# Ffrydiau_core.net
KiCad netlist of a schematic drawn in EAGLE
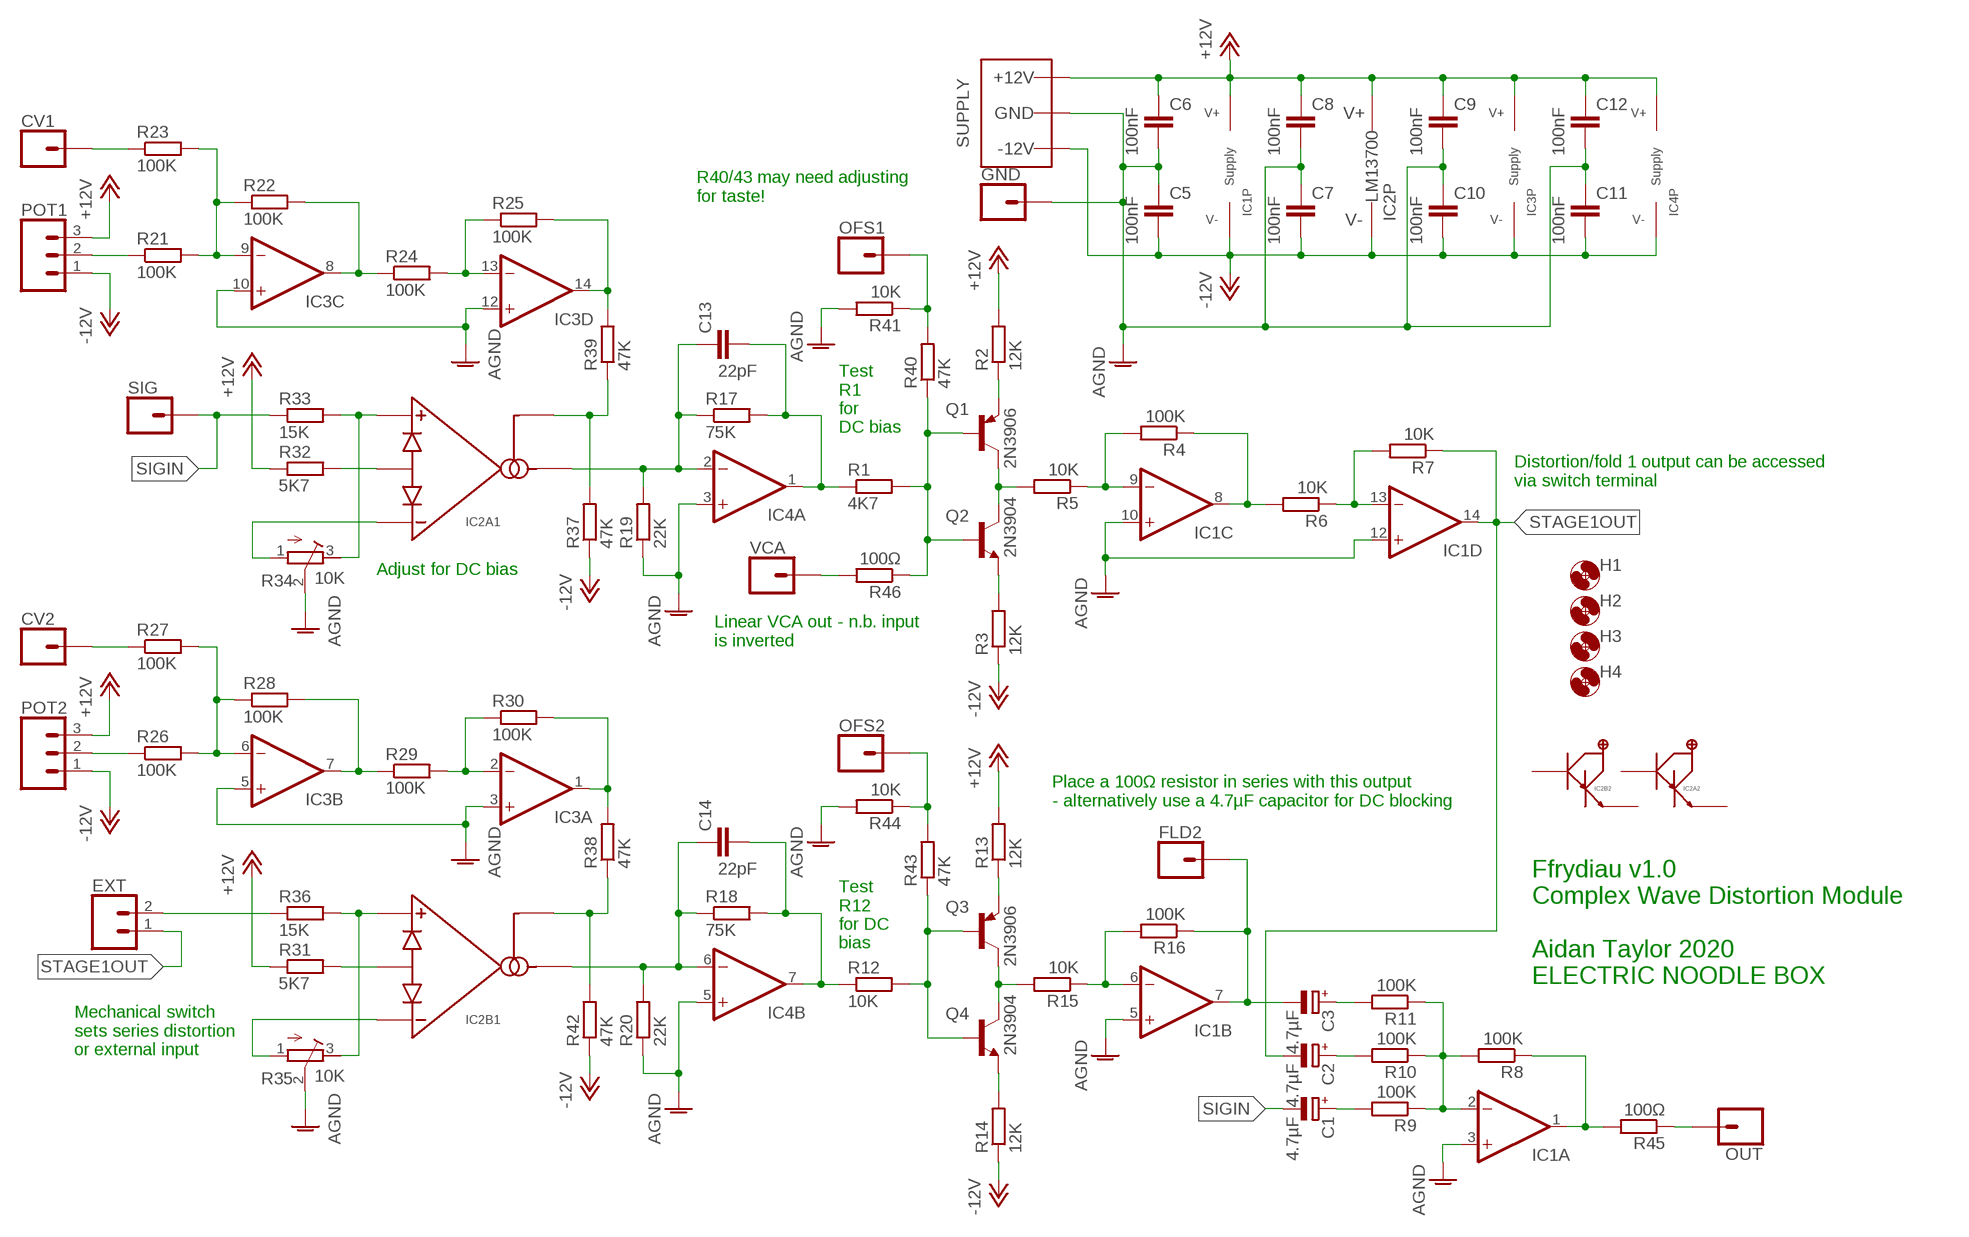
[diagram p0: schematic, sheet 1]

(export (version "E")
  (design (tool "Eeschema 10.0.6"))
  (components
    (comp (ref "C1")
      (value "4.7µF")
      (footprint "eagle-import:E2,5-6E")
      (libsource (lib "eagle-import") (part "CPOL-EUE2,5-6E"))
    )
    (comp (ref "C2")
      (value "4.7µF")
      (footprint "eagle-import:E2,5-6E")
      (libsource (lib "eagle-import") (part "CPOL-EUE2,5-6E"))
    )
    (comp (ref "C3")
      (value "4.7µF")
      (footprint "eagle-import:E2,5-6E")
      (libsource (lib "eagle-import") (part "CPOL-EUE2,5-6E"))
    )
    (comp (ref "C5")
      (value "100nF")
      (footprint "eagle-import:C050-025X075")
      (libsource (lib "eagle-import") (part "C-EU050-025X075"))
    )
    (comp (ref "C6")
      (value "100nF")
      (footprint "eagle-import:C050-025X075")
      (libsource (lib "eagle-import") (part "C-EU050-025X075"))
    )
    (comp (ref "C7")
      (value "100nF")
      (footprint "eagle-import:C050-025X075")
      (libsource (lib "eagle-import") (part "C-EU050-025X075"))
    )
    (comp (ref "C8")
      (value "100nF")
      (footprint "eagle-import:C050-025X075")
      (libsource (lib "eagle-import") (part "C-EU050-025X075"))
    )
    (comp (ref "C9")
      (value "100nF")
      (footprint "eagle-import:C050-025X075")
      (libsource (lib "eagle-import") (part "C-EU050-025X075"))
    )
    (comp (ref "C10")
      (value "100nF")
      (footprint "eagle-import:C050-025X075")
      (libsource (lib "eagle-import") (part "C-EU050-025X075"))
    )
    (comp (ref "C11")
      (value "100nF")
      (footprint "eagle-import:C050-025X075")
      (libsource (lib "eagle-import") (part "C-EU050-025X075"))
    )
    (comp (ref "C12")
      (value "100nF")
      (footprint "eagle-import:C050-025X075")
      (libsource (lib "eagle-import") (part "C-EU050-025X075"))
    )
    (comp (ref "C13")
      (value "22pF")
      (footprint "eagle-import:C050-025X075")
      (libsource (lib "eagle-import") (part "C-EU050-025X075"))
    )
    (comp (ref "C14")
      (value "22pF")
      (footprint "eagle-import:C050-025X075")
      (libsource (lib "eagle-import") (part "C-EU050-025X075"))
    )
    (comp (ref "CV1")
      (value "1XWIREPAD")
      (footprint "eagle-import:1X01")
      (libsource (lib "eagle-import") (part "1XWIREPAD"))
    )
    (comp (ref "CV2")
      (value "1XWIREPAD")
      (footprint "eagle-import:1X01")
      (libsource (lib "eagle-import") (part "1XWIREPAD"))
    )
    (comp (ref "EXT")
      (value "2XWIREPAD")
      (footprint "eagle-import:1X02")
      (libsource (lib "eagle-import") (part "2XWIREPAD"))
    )
    (comp (ref "FLD2")
      (value "1XWIREPAD")
      (footprint "eagle-import:1X01")
      (libsource (lib "eagle-import") (part "1XWIREPAD"))
    )
    (comp (ref "GND")
      (value "1XWIREPAD")
      (footprint "eagle-import:1X01")
      (libsource (lib "eagle-import") (part "1XWIREPAD"))
    )
    (comp (ref "H1")
      (value "MOUNT-HOLE3.2")
      (footprint "eagle-import:3,2")
      (libsource (lib "eagle-import") (part "MOUNT-HOLE3.2"))
    )
    (comp (ref "H2")
      (value "MOUNT-HOLE3.2")
      (footprint "eagle-import:3,2")
      (libsource (lib "eagle-import") (part "MOUNT-HOLE3.2"))
    )
    (comp (ref "H3")
      (value "MOUNT-HOLE3.2")
      (footprint "eagle-import:3,2")
      (libsource (lib "eagle-import") (part "MOUNT-HOLE3.2"))
    )
    (comp (ref "H4")
      (value "MOUNT-HOLE3.2")
      (footprint "eagle-import:3,2")
      (libsource (lib "eagle-import") (part "MOUNT-HOLE3.2"))
    )
    (comp (ref "IC1")
      (value "TL0X4DIL")
      (footprint "eagle-import:DIL14")
      (libsource (lib "eagle-import") (part "TL0X4DIL"))
    )
    (comp (ref "IC2")
      (value "LM13700DIL")
      (footprint "eagle-import:DIL16")
      (libsource (lib "eagle-import") (part "LM13700DIL"))
    )
    (comp (ref "IC3")
      (value "TL0X4DIL")
      (footprint "eagle-import:DIL14")
      (libsource (lib "eagle-import") (part "TL0X4DIL"))
    )
    (comp (ref "IC4")
      (value "TL0X2DIL")
      (footprint "eagle-import:DIL08")
      (libsource (lib "eagle-import") (part "TL0X2DIL"))
    )
    (comp (ref "OFS1")
      (value "1XWIREPAD")
      (footprint "eagle-import:1X01")
      (libsource (lib "eagle-import") (part "1XWIREPAD"))
    )
    (comp (ref "OFS2")
      (value "1XWIREPAD")
      (footprint "eagle-import:1X01")
      (libsource (lib "eagle-import") (part "1XWIREPAD"))
    )
    (comp (ref "OUT")
      (value "1XWIREPAD")
      (footprint "eagle-import:1X01")
      (libsource (lib "eagle-import") (part "1XWIREPAD"))
    )
    (comp (ref "POT1")
      (value "3XWIREPAD")
      (footprint "eagle-import:1X03")
      (libsource (lib "eagle-import") (part "3XWIREPAD"))
    )
    (comp (ref "POT2")
      (value "3XWIREPAD")
      (footprint "eagle-import:1X03")
      (libsource (lib "eagle-import") (part "3XWIREPAD"))
    )
    (comp (ref "Q1")
      (value "2N3906")
      (footprint "eagle-import:TO92")
      (libsource (lib "eagle-import") (part "2N3906"))
    )
    (comp (ref "Q2")
      (value "2N3904")
      (footprint "eagle-import:TO92")
      (libsource (lib "eagle-import") (part "2N3904"))
    )
    (comp (ref "Q3")
      (value "2N3906")
      (footprint "eagle-import:TO92")
      (libsource (lib "eagle-import") (part "2N3906"))
    )
    (comp (ref "Q4")
      (value "2N3904")
      (footprint "eagle-import:TO92")
      (libsource (lib "eagle-import") (part "2N3904"))
    )
    (comp (ref "R1")
      (value "4K7")
      (footprint "eagle-import:0207_10")
      (libsource (lib "eagle-import") (part "R-EU_0207/10"))
    )
    (comp (ref "R2")
      (value "12K")
      (footprint "eagle-import:0207_10")
      (libsource (lib "eagle-import") (part "R-EU_0207/10"))
    )
    (comp (ref "R3")
      (value "12K")
      (footprint "eagle-import:0207_10")
      (libsource (lib "eagle-import") (part "R-EU_0207/10"))
    )
    (comp (ref "R4")
      (value "100K")
      (footprint "eagle-import:0207_10")
      (libsource (lib "eagle-import") (part "R-EU_0207/10"))
    )
    (comp (ref "R5")
      (value "10K")
      (footprint "eagle-import:0207_10")
      (libsource (lib "eagle-import") (part "R-EU_0207/10"))
    )
    (comp (ref "R6")
      (value "10K")
      (footprint "eagle-import:0207_10")
      (libsource (lib "eagle-import") (part "R-EU_0207/10"))
    )
    (comp (ref "R7")
      (value "10K")
      (footprint "eagle-import:0207_10")
      (libsource (lib "eagle-import") (part "R-EU_0207/10"))
    )
    (comp (ref "R8")
      (value "100K")
      (footprint "eagle-import:0207_10")
      (libsource (lib "eagle-import") (part "R-EU_0207/10"))
    )
    (comp (ref "R9")
      (value "100K")
      (footprint "eagle-import:0207_10")
      (libsource (lib "eagle-import") (part "R-EU_0207/10"))
    )
    (comp (ref "R10")
      (value "100K")
      (footprint "eagle-import:0207_10")
      (libsource (lib "eagle-import") (part "R-EU_0207/10"))
    )
    (comp (ref "R11")
      (value "100K")
      (footprint "eagle-import:0207_10")
      (libsource (lib "eagle-import") (part "R-EU_0207/10"))
    )
    (comp (ref "R12")
      (value "10K")
      (footprint "eagle-import:0207_10")
      (libsource (lib "eagle-import") (part "R-EU_0207/10"))
    )
    (comp (ref "R13")
      (value "12K")
      (footprint "eagle-import:0207_10")
      (libsource (lib "eagle-import") (part "R-EU_0207/10"))
    )
    (comp (ref "R14")
      (value "12K")
      (footprint "eagle-import:0207_10")
      (libsource (lib "eagle-import") (part "R-EU_0207/10"))
    )
    (comp (ref "R15")
      (value "10K")
      (footprint "eagle-import:0207_10")
      (libsource (lib "eagle-import") (part "R-EU_0207/10"))
    )
    (comp (ref "R16")
      (value "100K")
      (footprint "eagle-import:0207_10")
      (libsource (lib "eagle-import") (part "R-EU_0207/10"))
    )
    (comp (ref "R17")
      (value "75K")
      (footprint "eagle-import:0207_10")
      (libsource (lib "eagle-import") (part "R-EU_0207/10"))
    )
    (comp (ref "R18")
      (value "75K")
      (footprint "eagle-import:0207_10")
      (libsource (lib "eagle-import") (part "R-EU_0207/10"))
    )
    (comp (ref "R19")
      (value "22K")
      (footprint "eagle-import:0207_10")
      (libsource (lib "eagle-import") (part "R-EU_0207/10"))
    )
    (comp (ref "R20")
      (value "22K")
      (footprint "eagle-import:0207_10")
      (libsource (lib "eagle-import") (part "R-EU_0207/10"))
    )
    (comp (ref "R21")
      (value "100K")
      (footprint "eagle-import:0207_10")
      (libsource (lib "eagle-import") (part "R-EU_0207/10"))
    )
    (comp (ref "R22")
      (value "100K")
      (footprint "eagle-import:0207_10")
      (libsource (lib "eagle-import") (part "R-EU_0207/10"))
    )
    (comp (ref "R23")
      (value "100K")
      (footprint "eagle-import:0207_10")
      (libsource (lib "eagle-import") (part "R-EU_0207/10"))
    )
    (comp (ref "R24")
      (value "100K")
      (footprint "eagle-import:0207_10")
      (libsource (lib "eagle-import") (part "R-EU_0207/10"))
    )
    (comp (ref "R25")
      (value "100K")
      (footprint "eagle-import:0207_10")
      (libsource (lib "eagle-import") (part "R-EU_0207/10"))
    )
    (comp (ref "R26")
      (value "100K")
      (footprint "eagle-import:0207_10")
      (libsource (lib "eagle-import") (part "R-EU_0207/10"))
    )
    (comp (ref "R27")
      (value "100K")
      (footprint "eagle-import:0207_10")
      (libsource (lib "eagle-import") (part "R-EU_0207/10"))
    )
    (comp (ref "R28")
      (value "100K")
      (footprint "eagle-import:0207_10")
      (libsource (lib "eagle-import") (part "R-EU_0207/10"))
    )
    (comp (ref "R29")
      (value "100K")
      (footprint "eagle-import:0207_10")
      (libsource (lib "eagle-import") (part "R-EU_0207/10"))
    )
    (comp (ref "R30")
      (value "100K")
      (footprint "eagle-import:0207_10")
      (libsource (lib "eagle-import") (part "R-EU_0207/10"))
    )
    (comp (ref "R31")
      (value "5K7")
      (footprint "eagle-import:0207_10")
      (libsource (lib "eagle-import") (part "R-EU_0207/10"))
    )
    (comp (ref "R32")
      (value "5K7")
      (footprint "eagle-import:0207_10")
      (libsource (lib "eagle-import") (part "R-EU_0207/10"))
    )
    (comp (ref "R33")
      (value "15K")
      (footprint "eagle-import:0207_10")
      (libsource (lib "eagle-import") (part "R-EU_0207/10"))
    )
    (comp (ref "R34")
      (value "10K")
      (footprint "eagle-import:RTRIM3296W")
      (libsource (lib "eagle-import") (part "R-TRIMM3296W"))
    )
    (comp (ref "R35")
      (value "10K")
      (footprint "eagle-import:RTRIM3296W")
      (libsource (lib "eagle-import") (part "R-TRIMM3296W"))
    )
    (comp (ref "R36")
      (value "15K")
      (footprint "eagle-import:0207_10")
      (libsource (lib "eagle-import") (part "R-EU_0207/10"))
    )
    (comp (ref "R37")
      (value "47K")
      (footprint "eagle-import:0207_10")
      (libsource (lib "eagle-import") (part "R-EU_0207/10"))
    )
    (comp (ref "R38")
      (value "47K")
      (footprint "eagle-import:0207_10")
      (libsource (lib "eagle-import") (part "R-EU_0207/10"))
    )
    (comp (ref "R39")
      (value "47K")
      (footprint "eagle-import:0207_10")
      (libsource (lib "eagle-import") (part "R-EU_0207/10"))
    )
    (comp (ref "R40")
      (value "47K")
      (footprint "eagle-import:0207_10")
      (libsource (lib "eagle-import") (part "R-EU_0207/10"))
    )
    (comp (ref "R41")
      (value "10K")
      (footprint "eagle-import:0207_10")
      (libsource (lib "eagle-import") (part "R-EU_0207/10"))
    )
    (comp (ref "R42")
      (value "47K")
      (footprint "eagle-import:0207_10")
      (libsource (lib "eagle-import") (part "R-EU_0207/10"))
    )
    (comp (ref "R43")
      (value "47K")
      (footprint "eagle-import:0207_10")
      (libsource (lib "eagle-import") (part "R-EU_0207/10"))
    )
    (comp (ref "R44")
      (value "10K")
      (footprint "eagle-import:0207_10")
      (libsource (lib "eagle-import") (part "R-EU_0207/10"))
    )
    (comp (ref "R45")
      (value "100Ω")
      (footprint "eagle-import:0207_10")
      (libsource (lib "eagle-import") (part "R-EU_0207/10"))
    )
    (comp (ref "R46")
      (value "100Ω")
      (footprint "eagle-import:0207_10")
      (libsource (lib "eagle-import") (part "R-EU_0207/10"))
    )
    (comp (ref "SIG")
      (value "1XWIREPAD")
      (footprint "eagle-import:1X01")
      (libsource (lib "eagle-import") (part "1XWIREPAD"))
    )
    (comp (ref "VCA")
      (value "1XWIREPAD")
      (footprint "eagle-import:1X01")
      (libsource (lib "eagle-import") (part "1XWIREPAD"))
    )
    (comp (ref "WP1")
      (value "COMBO_SUPPLY_HEADER")
      (footprint "eagle-import:COMBINED_POWER")
      (libsource (lib "eagle-import") (part "COMBO_SUPPLY_HEADER"))
    )
  )
  (nets
    (net (code "1") (name "+12V") (class "Default")
      (node (ref "C12") (pin "1") (pinfunction "1_1") (pintype "passive"))
      (node (ref "C6") (pin "1") (pinfunction "1_1") (pintype "passive"))
      (node (ref "C8") (pin "1") (pinfunction "1_1") (pintype "passive"))
      (node (ref "C9") (pin "1") (pinfunction "1_1") (pintype "passive"))
      (node (ref "IC1") (pin "4") (pinfunction "V+_4") (pintype "bidirectional"))
      (node (ref "IC2") (pin "11") (pinfunction "V+_11") (pintype "power_in"))
      (node (ref "IC3") (pin "4") (pinfunction "V+_4") (pintype "bidirectional"))
      (node (ref "IC4") (pin "8") (pinfunction "V+_8") (pintype "bidirectional"))
      (node (ref "POT1") (pin "3") (pinfunction "3_3") (pintype "passive"))
      (node (ref "POT2") (pin "3") (pinfunction "3_3") (pintype "passive"))
      (node (ref "R13") (pin "2") (pinfunction "2_2") (pintype "passive"))
      (node (ref "R2") (pin "2") (pinfunction "2_2") (pintype "passive"))
      (node (ref "R31") (pin "1") (pinfunction "1_1") (pintype "passive"))
      (node (ref "R32") (pin "1") (pinfunction "1_1") (pintype "passive"))
      (node (ref "WP1") (pin "V+1") (pinfunction "V++_V+1") (pintype "power_in"))
      (node (ref "WP1") (pin "V+2") (pinfunction "V++_V+2") (pintype "power_in"))
      (node (ref "WP1") (pin "V+3") (pinfunction "V++_V+3") (pintype "power_in"))
    )
    (net (code "2") (name "-12V") (class "Default")
      (node (ref "C10") (pin "2") (pinfunction "2_2") (pintype "passive"))
      (node (ref "C11") (pin "2") (pinfunction "2_2") (pintype "passive"))
      (node (ref "C5") (pin "2") (pinfunction "2_2") (pintype "passive"))
      (node (ref "C7") (pin "2") (pinfunction "2_2") (pintype "passive"))
      (node (ref "IC1") (pin "11") (pinfunction "V-_11") (pintype "bidirectional"))
      (node (ref "IC2") (pin "6") (pinfunction "V-_6") (pintype "power_in"))
      (node (ref "IC3") (pin "11") (pinfunction "V-_11") (pintype "bidirectional"))
      (node (ref "IC4") (pin "4") (pinfunction "V-_4") (pintype "bidirectional"))
      (node (ref "POT1") (pin "1") (pinfunction "1_1") (pintype "passive"))
      (node (ref "POT2") (pin "1") (pinfunction "1_1") (pintype "passive"))
      (node (ref "R14") (pin "1") (pinfunction "1_1") (pintype "passive"))
      (node (ref "R3") (pin "1") (pinfunction "1_1") (pintype "passive"))
      (node (ref "R37") (pin "1") (pinfunction "1_1") (pintype "passive"))
      (node (ref "R42") (pin "1") (pinfunction "1_1") (pintype "passive"))
      (node (ref "WP1") (pin "V-1") (pinfunction "V--_V-1") (pintype "power_in"))
      (node (ref "WP1") (pin "V-2") (pinfunction "V--_V-2") (pintype "power_in"))
      (node (ref "WP1") (pin "V-3") (pinfunction "V--_V-3") (pintype "power_in"))
    )
    (net (code "3") (name "AGND") (class "Default")
      (node (ref "C10") (pin "1") (pinfunction "1_1") (pintype "passive"))
      (node (ref "C11") (pin "1") (pinfunction "1_1") (pintype "passive"))
      (node (ref "C12") (pin "2") (pinfunction "2_2") (pintype "passive"))
      (node (ref "C5") (pin "1") (pinfunction "1_1") (pintype "passive"))
      (node (ref "C6") (pin "2") (pinfunction "2_2") (pintype "passive"))
      (node (ref "C7") (pin "1") (pinfunction "1_1") (pintype "passive"))
      (node (ref "C8") (pin "2") (pinfunction "2_2") (pintype "passive"))
      (node (ref "C9") (pin "2") (pinfunction "2_2") (pintype "passive"))
      (node (ref "GND") (pin "1") (pinfunction "1_1") (pintype "passive"))
      (node (ref "IC1") (pin "10") (pinfunction "+IN_10") (pintype "input"))
      (node (ref "IC1") (pin "12") (pinfunction "+IN_12") (pintype "input"))
      (node (ref "IC1") (pin "3") (pinfunction "+IN_3") (pintype "input"))
      (node (ref "IC1") (pin "5") (pinfunction "+IN_5") (pintype "input"))
      (node (ref "IC3") (pin "10") (pinfunction "+IN_10") (pintype "input"))
      (node (ref "IC3") (pin "12") (pinfunction "+IN_12") (pintype "input"))
      (node (ref "IC3") (pin "3") (pinfunction "+IN_3") (pintype "input"))
      (node (ref "IC3") (pin "5") (pinfunction "+IN_5") (pintype "input"))
      (node (ref "IC4") (pin "3") (pinfunction "+IN_3") (pintype "input"))
      (node (ref "IC4") (pin "5") (pinfunction "+IN_5") (pintype "input"))
      (node (ref "R19") (pin "1") (pinfunction "1_1") (pintype "passive"))
      (node (ref "R20") (pin "1") (pinfunction "1_1") (pintype "passive"))
      (node (ref "R34") (pin "2") (pinfunction "S_2") (pintype "passive"))
      (node (ref "R35") (pin "2") (pinfunction "S_2") (pintype "passive"))
      (node (ref "R41") (pin "2") (pinfunction "2_2") (pintype "passive"))
      (node (ref "R44") (pin "2") (pinfunction "2_2") (pintype "passive"))
      (node (ref "WP1") (pin "GND1") (pinfunction "AGND_GND1") (pintype "power_in"))
      (node (ref "WP1") (pin "GND2") (pinfunction "AGND_GND2") (pintype "power_in"))
      (node (ref "WP1") (pin "GND3") (pinfunction "AGND_GND3") (pintype "power_in"))
      (node (ref "WP1") (pin "GND4") (pinfunction "AGND_GND4") (pintype "power_in"))
      (node (ref "WP1") (pin "GND5") (pinfunction "AGND_GND5") (pintype "power_in"))
      (node (ref "WP1") (pin "GND6") (pinfunction "AGND_GND6") (pintype "power_in"))
      (node (ref "WP1") (pin "GND7") (pinfunction "AGND_GND7") (pintype "power_in"))
      (node (ref "WP1") (pin "GND8") (pinfunction "AGND_GND8") (pintype "power_in"))
    )
    (net (code "4") (name "Net-(C1-Pad+)") (class "Default")
      (node (ref "C1") (pin "+") (pinfunction "+_+") (pintype "passive"))
      (node (ref "R9") (pin "2") (pinfunction "2_2") (pintype "passive"))
    )
    (net (code "5") (name "Net-(C2-Pad+)") (class "Default")
      (node (ref "C2") (pin "+") (pinfunction "+_+") (pintype "passive"))
      (node (ref "R10") (pin "2") (pinfunction "2_2") (pintype "passive"))
    )
    (net (code "6") (name "Net-(C3-Pad+)") (class "Default")
      (node (ref "C3") (pin "+") (pinfunction "+_+") (pintype "passive"))
      (node (ref "R11") (pin "2") (pinfunction "2_2") (pintype "passive"))
    )
    (net (code "7") (name "Net-(CV1-Pad1)") (class "Default")
      (node (ref "CV1") (pin "1") (pinfunction "1_1") (pintype "passive"))
      (node (ref "R23") (pin "1") (pinfunction "1_1") (pintype "passive"))
    )
    (net (code "8") (name "Net-(CV2-Pad1)") (class "Default")
      (node (ref "CV2") (pin "1") (pinfunction "1_1") (pintype "passive"))
      (node (ref "R27") (pin "1") (pinfunction "1_1") (pintype "passive"))
    )
    (net (code "9") (name "Net-(EXT-Pad2)") (class "Default")
      (node (ref "EXT") (pin "2") (pinfunction "2_2") (pintype "passive"))
      (node (ref "R36") (pin "1") (pinfunction "1_1") (pintype "passive"))
    )
    (net (code "10") (name "Net-(IC1A--IN)") (class "Default")
      (node (ref "IC1") (pin "2") (pinfunction "-IN_2") (pintype "input"))
      (node (ref "R10") (pin "1") (pinfunction "1_1") (pintype "passive"))
      (node (ref "R11") (pin "1") (pinfunction "1_1") (pintype "passive"))
      (node (ref "R8") (pin "2") (pinfunction "2_2") (pintype "passive"))
      (node (ref "R9") (pin "1") (pinfunction "1_1") (pintype "passive"))
    )
    (net (code "11") (name "Net-(IC1A-OUT)") (class "Default")
      (node (ref "IC1") (pin "1") (pinfunction "OUT_1") (pintype "output"))
      (node (ref "R45") (pin "2") (pinfunction "2_2") (pintype "passive"))
      (node (ref "R8") (pin "1") (pinfunction "1_1") (pintype "passive"))
    )
    (net (code "12") (name "Net-(IC1B--IN)") (class "Default")
      (node (ref "IC1") (pin "6") (pinfunction "-IN_6") (pintype "input"))
      (node (ref "R15") (pin "1") (pinfunction "1_1") (pintype "passive"))
      (node (ref "R16") (pin "2") (pinfunction "2_2") (pintype "passive"))
    )
    (net (code "13") (name "Net-(IC1B-OUT)") (class "Default")
      (node (ref "C3") (pin "-") (pinfunction "-_-") (pintype "passive"))
      (node (ref "FLD2") (pin "1") (pinfunction "1_1") (pintype "passive"))
      (node (ref "IC1") (pin "7") (pinfunction "OUT_7") (pintype "output"))
      (node (ref "R16") (pin "1") (pinfunction "1_1") (pintype "passive"))
    )
    (net (code "14") (name "Net-(IC1C--IN)") (class "Default")
      (node (ref "IC1") (pin "9") (pinfunction "-IN_9") (pintype "input"))
      (node (ref "R4") (pin "2") (pinfunction "2_2") (pintype "passive"))
      (node (ref "R5") (pin "1") (pinfunction "1_1") (pintype "passive"))
    )
    (net (code "15") (name "Net-(IC1C-OUT)") (class "Default")
      (node (ref "IC1") (pin "8") (pinfunction "OUT_8") (pintype "output"))
      (node (ref "R4") (pin "1") (pinfunction "1_1") (pintype "passive"))
      (node (ref "R6") (pin "2") (pinfunction "2_2") (pintype "passive"))
    )
    (net (code "16") (name "Net-(IC1D--IN)") (class "Default")
      (node (ref "IC1") (pin "13") (pinfunction "-IN_13") (pintype "input"))
      (node (ref "R6") (pin "1") (pinfunction "1_1") (pintype "passive"))
      (node (ref "R7") (pin "2") (pinfunction "2_2") (pintype "passive"))
    )
    (net (code "17") (name "Net-(IC2A-AMP+)") (class "Default")
      (node (ref "IC2") (pin "3") (pinfunction "AMP+_3") (pintype "input"))
      (node (ref "R33") (pin "2") (pinfunction "2_2") (pintype "passive"))
      (node (ref "R34") (pin "3") (pinfunction "E_3") (pintype "passive"))
    )
    (net (code "18") (name "Net-(IC2A-AMP-)") (class "Default")
      (node (ref "IC2") (pin "4") (pinfunction "AMP-_4") (pintype "input"))
      (node (ref "R34") (pin "1") (pinfunction "A_1") (pintype "passive"))
    )
    (net (code "19") (name "Net-(IC2A-AMPBIAS)") (class "Default")
      (node (ref "IC2") (pin "1") (pinfunction "AMPBIAS_1") (pintype "input"))
      (node (ref "R37") (pin "2") (pinfunction "2_2") (pintype "passive"))
      (node (ref "R39") (pin "1") (pinfunction "1_1") (pintype "passive"))
    )
    (net (code "20") (name "Net-(IC2A-AMPOUT)") (class "Default")
      (node (ref "C13") (pin "1") (pinfunction "1_1") (pintype "passive"))
      (node (ref "IC2") (pin "5") (pinfunction "AMPOUT_5") (pintype "output"))
      (node (ref "IC4") (pin "2") (pinfunction "-IN_2") (pintype "input"))
      (node (ref "R17") (pin "1") (pinfunction "1_1") (pintype "passive"))
      (node (ref "R19") (pin "2") (pinfunction "2_2") (pintype "passive"))
    )
    (net (code "21") (name "Net-(IC2A-DIODES)") (class "Default")
      (node (ref "IC2") (pin "2") (pinfunction "DIODES_2") (pintype "input"))
      (node (ref "R32") (pin "2") (pinfunction "2_2") (pintype "passive"))
    )
    (net (code "22") (name "Net-(IC2C-AMP+)") (class "Default")
      (node (ref "IC2") (pin "14") (pinfunction "AMP+_14") (pintype "input"))
      (node (ref "R35") (pin "3") (pinfunction "E_3") (pintype "passive"))
      (node (ref "R36") (pin "2") (pinfunction "2_2") (pintype "passive"))
    )
    (net (code "23") (name "Net-(IC2C-AMP-)") (class "Default")
      (node (ref "IC2") (pin "13") (pinfunction "AMP-_13") (pintype "input"))
      (node (ref "R35") (pin "1") (pinfunction "A_1") (pintype "passive"))
    )
    (net (code "24") (name "Net-(IC2C-AMPBIAS)") (class "Default")
      (node (ref "IC2") (pin "16") (pinfunction "AMPBIAS_16") (pintype "input"))
      (node (ref "R38") (pin "1") (pinfunction "1_1") (pintype "passive"))
      (node (ref "R42") (pin "2") (pinfunction "2_2") (pintype "passive"))
    )
    (net (code "25") (name "Net-(IC2C-AMPOUT)") (class "Default")
      (node (ref "C14") (pin "1") (pinfunction "1_1") (pintype "passive"))
      (node (ref "IC2") (pin "12") (pinfunction "AMPOUT_12") (pintype "output"))
      (node (ref "IC4") (pin "6") (pinfunction "-IN_6") (pintype "input"))
      (node (ref "R18") (pin "1") (pinfunction "1_1") (pintype "passive"))
      (node (ref "R20") (pin "2") (pinfunction "2_2") (pintype "passive"))
    )
    (net (code "26") (name "Net-(IC2C-DIODES)") (class "Default")
      (node (ref "IC2") (pin "15") (pinfunction "DIODES_15") (pintype "input"))
      (node (ref "R31") (pin "2") (pinfunction "2_2") (pintype "passive"))
    )
    (net (code "27") (name "Net-(IC3A--IN)") (class "Default")
      (node (ref "IC3") (pin "2") (pinfunction "-IN_2") (pintype "input"))
      (node (ref "R29") (pin "2") (pinfunction "2_2") (pintype "passive"))
      (node (ref "R30") (pin "1") (pinfunction "1_1") (pintype "passive"))
    )
    (net (code "28") (name "Net-(IC3A-OUT)") (class "Default")
      (node (ref "IC3") (pin "1") (pinfunction "OUT_1") (pintype "output"))
      (node (ref "R30") (pin "2") (pinfunction "2_2") (pintype "passive"))
      (node (ref "R38") (pin "2") (pinfunction "2_2") (pintype "passive"))
    )
    (net (code "29") (name "Net-(IC3B--IN)") (class "Default")
      (node (ref "IC3") (pin "6") (pinfunction "-IN_6") (pintype "input"))
      (node (ref "R26") (pin "2") (pinfunction "2_2") (pintype "passive"))
      (node (ref "R27") (pin "2") (pinfunction "2_2") (pintype "passive"))
      (node (ref "R28") (pin "1") (pinfunction "1_1") (pintype "passive"))
    )
    (net (code "30") (name "Net-(IC3B-OUT)") (class "Default")
      (node (ref "IC3") (pin "7") (pinfunction "OUT_7") (pintype "output"))
      (node (ref "R28") (pin "2") (pinfunction "2_2") (pintype "passive"))
      (node (ref "R29") (pin "1") (pinfunction "1_1") (pintype "passive"))
    )
    (net (code "31") (name "Net-(IC3C--IN)") (class "Default")
      (node (ref "IC3") (pin "9") (pinfunction "-IN_9") (pintype "input"))
      (node (ref "R21") (pin "2") (pinfunction "2_2") (pintype "passive"))
      (node (ref "R22") (pin "1") (pinfunction "1_1") (pintype "passive"))
      (node (ref "R23") (pin "2") (pinfunction "2_2") (pintype "passive"))
    )
    (net (code "32") (name "Net-(IC3C-OUT)") (class "Default")
      (node (ref "IC3") (pin "8") (pinfunction "OUT_8") (pintype "output"))
      (node (ref "R22") (pin "2") (pinfunction "2_2") (pintype "passive"))
      (node (ref "R24") (pin "1") (pinfunction "1_1") (pintype "passive"))
    )
    (net (code "33") (name "Net-(IC3D--IN)") (class "Default")
      (node (ref "IC3") (pin "13") (pinfunction "-IN_13") (pintype "input"))
      (node (ref "R24") (pin "2") (pinfunction "2_2") (pintype "passive"))
      (node (ref "R25") (pin "1") (pinfunction "1_1") (pintype "passive"))
    )
    (net (code "34") (name "Net-(IC3D-OUT)") (class "Default")
      (node (ref "IC3") (pin "14") (pinfunction "OUT_14") (pintype "output"))
      (node (ref "R25") (pin "2") (pinfunction "2_2") (pintype "passive"))
      (node (ref "R39") (pin "2") (pinfunction "2_2") (pintype "passive"))
    )
    (net (code "35") (name "Net-(IC4A-OUT)") (class "Default")
      (node (ref "C13") (pin "2") (pinfunction "2_2") (pintype "passive"))
      (node (ref "IC4") (pin "1") (pinfunction "OUT_1") (pintype "output"))
      (node (ref "R1") (pin "1") (pinfunction "1_1") (pintype "passive"))
      (node (ref "R17") (pin "2") (pinfunction "2_2") (pintype "passive"))
    )
    (net (code "36") (name "Net-(IC4B-OUT)") (class "Default")
      (node (ref "C14") (pin "2") (pinfunction "2_2") (pintype "passive"))
      (node (ref "IC4") (pin "7") (pinfunction "OUT_7") (pintype "output"))
      (node (ref "R12") (pin "1") (pinfunction "1_1") (pintype "passive"))
      (node (ref "R18") (pin "2") (pinfunction "2_2") (pintype "passive"))
    )
    (net (code "37") (name "Net-(OFS1-Pad1)") (class "Default")
      (node (ref "OFS1") (pin "1") (pinfunction "1_1") (pintype "passive"))
      (node (ref "R40") (pin "2") (pinfunction "2_2") (pintype "passive"))
      (node (ref "R41") (pin "1") (pinfunction "1_1") (pintype "passive"))
    )
    (net (code "38") (name "Net-(OFS2-Pad1)") (class "Default")
      (node (ref "OFS2") (pin "1") (pinfunction "1_1") (pintype "passive"))
      (node (ref "R43") (pin "2") (pinfunction "2_2") (pintype "passive"))
      (node (ref "R44") (pin "1") (pinfunction "1_1") (pintype "passive"))
    )
    (net (code "39") (name "Net-(OUT-Pad1)") (class "Default")
      (node (ref "OUT") (pin "1") (pinfunction "1_1") (pintype "passive"))
      (node (ref "R45") (pin "1") (pinfunction "1_1") (pintype "passive"))
    )
    (net (code "40") (name "Net-(POT1-Pad2)") (class "Default")
      (node (ref "POT1") (pin "2") (pinfunction "2_2") (pintype "passive"))
      (node (ref "R21") (pin "1") (pinfunction "1_1") (pintype "passive"))
    )
    (net (code "41") (name "Net-(POT2-Pad2)") (class "Default")
      (node (ref "POT2") (pin "2") (pinfunction "2_2") (pintype "passive"))
      (node (ref "R26") (pin "1") (pinfunction "1_1") (pintype "passive"))
    )
    (net (code "42") (name "Net-(Q1-B)") (class "Default")
      (node (ref "Q1") (pin "2") (pinfunction "B_2") (pintype "passive"))
      (node (ref "Q2") (pin "2") (pinfunction "B_2") (pintype "passive"))
      (node (ref "R1") (pin "2") (pinfunction "2_2") (pintype "passive"))
      (node (ref "R40") (pin "1") (pinfunction "1_1") (pintype "passive"))
      (node (ref "R46") (pin "1") (pinfunction "1_1") (pintype "passive"))
    )
    (net (code "43") (name "Net-(Q1-C)") (class "Default")
      (node (ref "Q1") (pin "1") (pinfunction "C_1") (pintype "passive"))
      (node (ref "Q2") (pin "1") (pinfunction "C_1") (pintype "passive"))
      (node (ref "R5") (pin "2") (pinfunction "2_2") (pintype "passive"))
    )
    (net (code "44") (name "Net-(Q1-E)") (class "Default")
      (node (ref "Q1") (pin "3") (pinfunction "E_3") (pintype "passive"))
      (node (ref "R2") (pin "1") (pinfunction "1_1") (pintype "passive"))
    )
    (net (code "45") (name "Net-(Q2-E)") (class "Default")
      (node (ref "Q2") (pin "3") (pinfunction "E_3") (pintype "passive"))
      (node (ref "R3") (pin "2") (pinfunction "2_2") (pintype "passive"))
    )
    (net (code "46") (name "Net-(Q3-B)") (class "Default")
      (node (ref "Q3") (pin "2") (pinfunction "B_2") (pintype "passive"))
      (node (ref "Q4") (pin "2") (pinfunction "B_2") (pintype "passive"))
      (node (ref "R12") (pin "2") (pinfunction "2_2") (pintype "passive"))
      (node (ref "R43") (pin "1") (pinfunction "1_1") (pintype "passive"))
    )
    (net (code "47") (name "Net-(Q3-C)") (class "Default")
      (node (ref "Q3") (pin "1") (pinfunction "C_1") (pintype "passive"))
      (node (ref "Q4") (pin "1") (pinfunction "C_1") (pintype "passive"))
      (node (ref "R15") (pin "2") (pinfunction "2_2") (pintype "passive"))
    )
    (net (code "48") (name "Net-(Q3-E)") (class "Default")
      (node (ref "Q3") (pin "3") (pinfunction "E_3") (pintype "passive"))
      (node (ref "R13") (pin "1") (pinfunction "1_1") (pintype "passive"))
    )
    (net (code "49") (name "Net-(Q4-E)") (class "Default")
      (node (ref "Q4") (pin "3") (pinfunction "E_3") (pintype "passive"))
      (node (ref "R14") (pin "2") (pinfunction "2_2") (pintype "passive"))
    )
    (net (code "50") (name "Net-(R46-Pad2)") (class "Default")
      (node (ref "R46") (pin "2") (pinfunction "2_2") (pintype "passive"))
      (node (ref "VCA") (pin "1") (pinfunction "1_1") (pintype "passive"))
    )
    (net (code "51") (name "SIGIN") (class "Default")
      (node (ref "C1") (pin "-") (pinfunction "-_-") (pintype "passive"))
      (node (ref "R33") (pin "1") (pinfunction "1_1") (pintype "passive"))
      (node (ref "SIG") (pin "1") (pinfunction "1_1") (pintype "passive"))
    )
    (net (code "52") (name "STAGE1OUT") (class "Default")
      (node (ref "C2") (pin "-") (pinfunction "-_-") (pintype "passive"))
      (node (ref "EXT") (pin "1") (pinfunction "1_1") (pintype "passive"))
      (node (ref "IC1") (pin "14") (pinfunction "OUT_14") (pintype "output"))
      (node (ref "R7") (pin "1") (pinfunction "1_1") (pintype "passive"))
    )
    (net (code "53") (name "unconnected-(IC2B-BUFF_IN-Pad7)") (class "Default")
      (node (ref "IC2") (pin "7") (pinfunction "BUFF_IN_7") (pintype "input"))
    )
    (net (code "54") (name "unconnected-(IC2B-BUFF_OUT-Pad8)") (class "Default")
      (node (ref "IC2") (pin "8") (pinfunction "BUFF_OUT_8") (pintype "bidirectional"))
    )
    (net (code "55") (name "unconnected-(IC2D-BUFF_IN-Pad10)") (class "Default")
      (node (ref "IC2") (pin "10") (pinfunction "BUFF_IN_10") (pintype "input"))
    )
    (net (code "56") (name "unconnected-(IC2D-BUFF_OUT-Pad9)") (class "Default")
      (node (ref "IC2") (pin "9") (pinfunction "BUFF_OUT_9") (pintype "bidirectional"))
    )
  )
)
